# CJMCU-FT232HQ-PROGRAMMER.net
KiCad netlist of a schematic drawn in Altium Designer
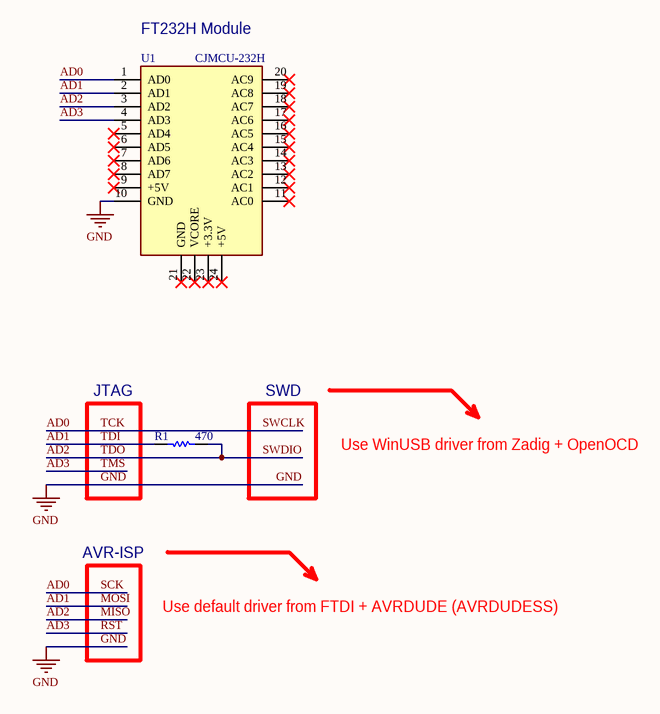
[diagram p0: CJMCU-FT232HQ-PROGRAMMER.SchDoc]

(export (version "E")
  (design (tool "Eeschema 10.0.6"))
  (components
    (comp (ref "R1")
      (value "470")
      (footprint "R0805")
      (description "RES SMD 10K OHM 1% 1/8W 0805")
      (fields (field (name "TOLERANCE") "1%") (field (name "Comment") "CRG0805F10K"))
      (libsource (lib "CustomLib-Package") (part "RESISTOR"))
    )
    (comp (ref "U1")
      (value "CJMCU-232H")
      (footprint "CJMCU-232H")
      (description "CNMCU FT232HQ Breakout Board")
      (libsource (lib "CustomLib-Package") (part "CJMCU-232H"))
    )
  )
  (nets
    (net (code "1") (name "/AD0") (class "Default")
      (node (ref "U1") (pin "1") (pinfunction "AD0_1") (pintype "passive"))
    )
    (net (code "2") (name "/AD1") (class "Default")
      (node (ref "R1") (pin "2") (pinfunction "2_2") (pintype "passive"))
      (node (ref "U1") (pin "2") (pinfunction "AD1_2") (pintype "passive"))
    )
    (net (code "3") (name "/AD2") (class "Default")
      (node (ref "R1") (pin "1") (pinfunction "1_1") (pintype "passive"))
      (node (ref "U1") (pin "3") (pinfunction "AD2_3") (pintype "passive"))
    )
    (net (code "4") (name "/AD3") (class "Default")
      (node (ref "U1") (pin "4") (pinfunction "AD3_4") (pintype "passive"))
    )
    (net (code "5") (name "GND") (class "Default")
      (node (ref "U1") (pin "10") (pinfunction "GND_10") (pintype "passive"))
    )
    (net (code "6") (name "unconnected-(U1-+3.3V-Pad23)") (class "Default")
      (node (ref "U1") (pin "23") (pinfunction "+3.3V_23") (pintype "passive+no_connect"))
    )
    (net (code "7") (name "unconnected-(U1-+5V-Pad9)") (class "Default")
      (node (ref "U1") (pin "9") (pinfunction "+5V_9") (pintype "passive+no_connect"))
    )
    (net (code "8") (name "unconnected-(U1-+5V-Pad24)") (class "Default")
      (node (ref "U1") (pin "24") (pinfunction "+5V_24") (pintype "passive+no_connect"))
    )
    (net (code "9") (name "unconnected-(U1-AC0-Pad11)") (class "Default")
      (node (ref "U1") (pin "11") (pinfunction "AC0_11") (pintype "passive+no_connect"))
    )
    (net (code "10") (name "unconnected-(U1-AC1-Pad12)") (class "Default")
      (node (ref "U1") (pin "12") (pinfunction "AC1_12") (pintype "passive+no_connect"))
    )
    (net (code "11") (name "unconnected-(U1-AC2-Pad13)") (class "Default")
      (node (ref "U1") (pin "13") (pinfunction "AC2_13") (pintype "passive+no_connect"))
    )
    (net (code "12") (name "unconnected-(U1-AC3-Pad14)") (class "Default")
      (node (ref "U1") (pin "14") (pinfunction "AC3_14") (pintype "passive+no_connect"))
    )
    (net (code "13") (name "unconnected-(U1-AC4-Pad15)") (class "Default")
      (node (ref "U1") (pin "15") (pinfunction "AC4_15") (pintype "passive+no_connect"))
    )
    (net (code "14") (name "unconnected-(U1-AC5-Pad16)") (class "Default")
      (node (ref "U1") (pin "16") (pinfunction "AC5_16") (pintype "passive+no_connect"))
    )
    (net (code "15") (name "unconnected-(U1-AC6-Pad17)") (class "Default")
      (node (ref "U1") (pin "17") (pinfunction "AC6_17") (pintype "passive+no_connect"))
    )
    (net (code "16") (name "unconnected-(U1-AC7-Pad18)") (class "Default")
      (node (ref "U1") (pin "18") (pinfunction "AC7_18") (pintype "passive+no_connect"))
    )
    (net (code "17") (name "unconnected-(U1-AC8-Pad19)") (class "Default")
      (node (ref "U1") (pin "19") (pinfunction "AC8_19") (pintype "passive+no_connect"))
    )
    (net (code "18") (name "unconnected-(U1-AC9-Pad20)") (class "Default")
      (node (ref "U1") (pin "20") (pinfunction "AC9_20") (pintype "passive+no_connect"))
    )
    (net (code "19") (name "unconnected-(U1-AD4-Pad5)") (class "Default")
      (node (ref "U1") (pin "5") (pinfunction "AD4_5") (pintype "passive+no_connect"))
    )
    (net (code "20") (name "unconnected-(U1-AD5-Pad6)") (class "Default")
      (node (ref "U1") (pin "6") (pinfunction "AD5_6") (pintype "passive+no_connect"))
    )
    (net (code "21") (name "unconnected-(U1-AD6-Pad7)") (class "Default")
      (node (ref "U1") (pin "7") (pinfunction "AD6_7") (pintype "passive+no_connect"))
    )
    (net (code "22") (name "unconnected-(U1-AD7-Pad8)") (class "Default")
      (node (ref "U1") (pin "8") (pinfunction "AD7_8") (pintype "passive+no_connect"))
    )
    (net (code "23") (name "unconnected-(U1-GND-Pad21)") (class "Default")
      (node (ref "U1") (pin "21") (pinfunction "GND_21") (pintype "passive+no_connect"))
    )
    (net (code "24") (name "unconnected-(U1-VCORE-Pad22)") (class "Default")
      (node (ref "U1") (pin "22") (pinfunction "VCORE_22") (pintype "passive+no_connect"))
    )
  )
)
